# merkur-osdgruve-42-schield.net
KiCad netlist of a schematic drawn in EAGLE
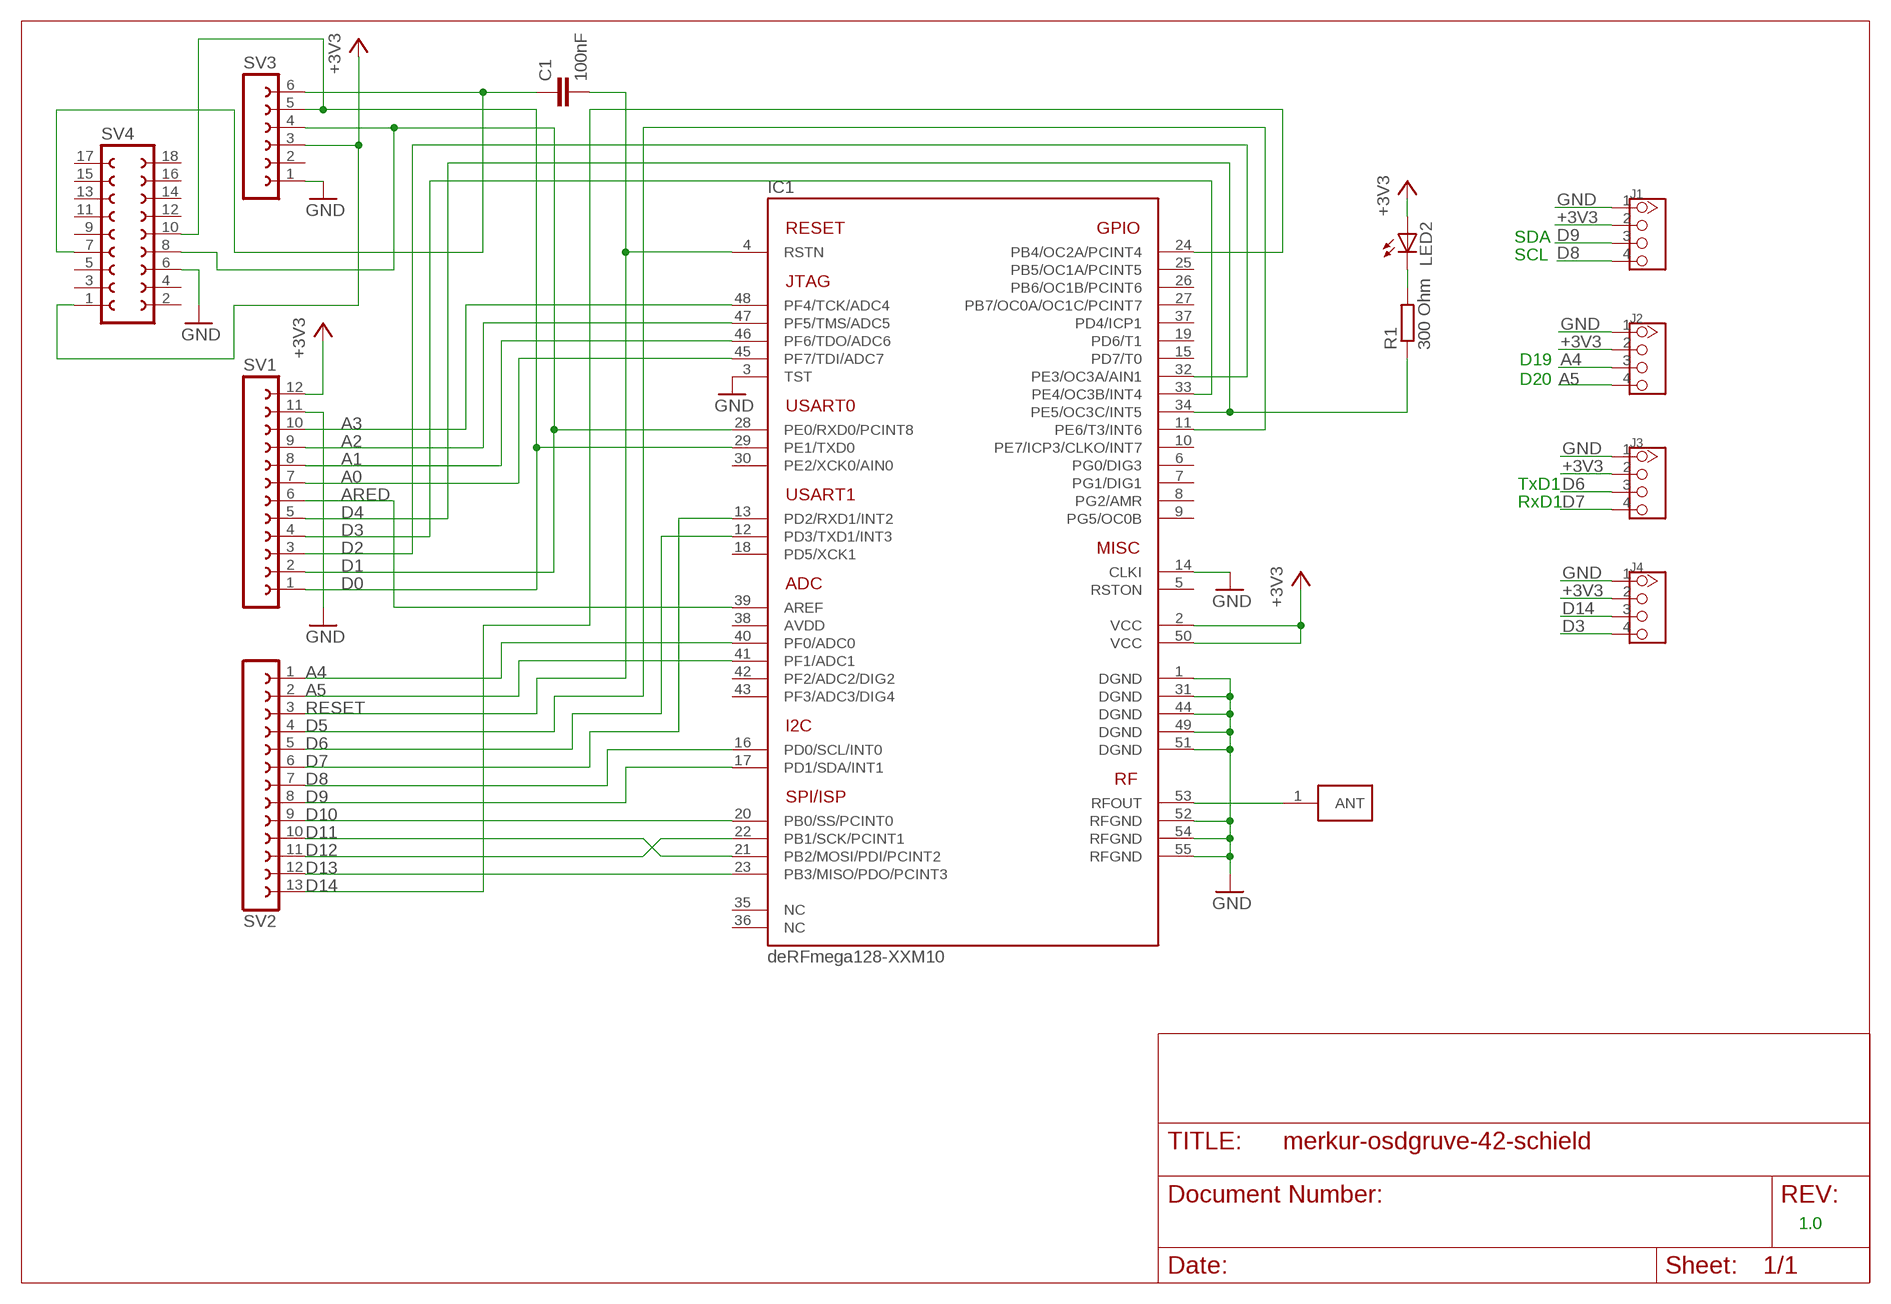
[diagram p0: schematic, sheet 1]

(export (version "E")
  (design (tool "Eeschema 10.0.6"))
  (components
    (comp (ref "C1")
      (value "100nF")
      (footprint "eagle-import:C0603")
      (libsource (lib "eagle-import") (part "C-EUC0603"))
    )
    (comp (ref "IC1")
      (value "DERFMEGA128-XXM10")
      (footprint "eagle-import:A-M10")
      (libsource (lib "eagle-import") (part "DERFMEGA128-XXM10"))
    )
    (comp (ref "J1")
      (value "CONNECTOR_TWIG-4P-2.0-2.0")
      (footprint "eagle-import:CONNECTOR_4P-2.0")
      (libsource (lib "eagle-import") (part "CONNECTOR_TWIG-4P-2.0-2.0"))
    )
    (comp (ref "J2")
      (value "CONNECTOR_TWIG-4P-2.0-2.0")
      (footprint "eagle-import:CONNECTOR_4P-2.0")
      (libsource (lib "eagle-import") (part "CONNECTOR_TWIG-4P-2.0-2.0"))
    )
    (comp (ref "J3")
      (value "CONNECTOR_TWIG-4P-2.0-2.0")
      (footprint "eagle-import:CONNECTOR_4P-2.0")
      (libsource (lib "eagle-import") (part "CONNECTOR_TWIG-4P-2.0-2.0"))
    )
    (comp (ref "J4")
      (value "CONNECTOR_TWIG-4P-2.0-2.0")
      (footprint "eagle-import:CONNECTOR_4P-2.0")
      (libsource (lib "eagle-import") (part "CONNECTOR_TWIG-4P-2.0-2.0"))
    )
    (comp (ref "LED2")
      (value "LEDCHIP-LED0603")
      (footprint "eagle-import:CHIP-LED0603")
      (libsource (lib "eagle-import") (part "LEDCHIP-LED0603"))
    )
    (comp (ref "R1")
      (value "300 Ohm")
      (footprint "eagle-import:R0603")
      (libsource (lib "eagle-import") (part "R-EU_R0603"))
    )
    (comp (ref "SV1")
      (value "FE12-1")
      (footprint "eagle-import:FE12")
      (libsource (lib "eagle-import") (part "FE12-1"))
    )
    (comp (ref "SV2")
      (value "FE13-1")
      (footprint "eagle-import:FE13")
      (libsource (lib "eagle-import") (part "FE13-1"))
    )
    (comp (ref "SV3")
      (value "FE06-1")
      (footprint "eagle-import:FE06")
      (libsource (lib "eagle-import") (part "FE06-1"))
    )
    (comp (ref "SV4")
      (value "FE09-2")
      (footprint "eagle-import:FE09-2")
      (libsource (lib "eagle-import") (part "FE09-2"))
    )
    (comp (ref "U$1")
      (value "PAD")
      (footprint "eagle-import:FE05-1")
      (libsource (lib "eagle-import") (part "PAD"))
    )
  )
  (nets
    (net (code "1") (name "+3V3") (class "Default")
      (node (ref "IC1") (pin "2") (pinfunction "VCC_2") (pintype "power_in"))
      (node (ref "IC1") (pin "50") (pinfunction "VCC_50") (pintype "power_in"))
      (node (ref "J1") (pin "2") (pinfunction "2_2") (pintype "bidirectional"))
      (node (ref "J2") (pin "2") (pinfunction "2_2") (pintype "bidirectional"))
      (node (ref "J3") (pin "2") (pinfunction "2_2") (pintype "bidirectional"))
      (node (ref "J4") (pin "2") (pinfunction "2_2") (pintype "bidirectional"))
      (node (ref "LED2") (pin "A") (pinfunction "A_A") (pintype "passive"))
      (node (ref "SV1") (pin "12") (pinfunction "12_12") (pintype "passive"))
      (node (ref "SV3") (pin "3") (pinfunction "3_3") (pintype "passive"))
      (node (ref "SV4") (pin "1") (pinfunction "1_1") (pintype "passive"))
    )
    (net (code "2") (name "/A0") (class "Default")
      (node (ref "IC1") (pin "45") (pinfunction "PF7/TDI/ADC7_45") (pintype "bidirectional"))
      (node (ref "SV1") (pin "7") (pinfunction "7_7") (pintype "passive"))
    )
    (net (code "3") (name "/A1") (class "Default")
      (node (ref "IC1") (pin "46") (pinfunction "PF6/TDO/ADC6_46") (pintype "bidirectional"))
      (node (ref "SV1") (pin "8") (pinfunction "8_8") (pintype "passive"))
    )
    (net (code "4") (name "/A2") (class "Default")
      (node (ref "IC1") (pin "47") (pinfunction "PF5/TMS/ADC5_47") (pintype "bidirectional"))
      (node (ref "SV1") (pin "9") (pinfunction "9_9") (pintype "passive"))
    )
    (net (code "5") (name "/A3") (class "Default")
      (node (ref "IC1") (pin "48") (pinfunction "PF4/TCK/ADC4_48") (pintype "bidirectional"))
      (node (ref "SV1") (pin "10") (pinfunction "10_10") (pintype "passive"))
    )
    (net (code "6") (name "/A4") (class "Default")
      (node (ref "IC1") (pin "40") (pinfunction "PF0/ADC0_40") (pintype "bidirectional"))
      (node (ref "J2") (pin "3") (pinfunction "3_3") (pintype "bidirectional"))
      (node (ref "SV2") (pin "1") (pinfunction "1_1") (pintype "passive"))
    )
    (net (code "7") (name "/A5") (class "Default")
      (node (ref "IC1") (pin "41") (pinfunction "PF1/ADC1_41") (pintype "bidirectional"))
      (node (ref "J2") (pin "4") (pinfunction "4_4") (pintype "bidirectional"))
      (node (ref "SV2") (pin "2") (pinfunction "2_2") (pintype "passive"))
    )
    (net (code "8") (name "/ARED") (class "Default")
      (node (ref "IC1") (pin "39") (pinfunction "AREF_39") (pintype "bidirectional"))
      (node (ref "SV1") (pin "6") (pinfunction "6_6") (pintype "passive"))
    )
    (net (code "9") (name "/AVDD") (class "Default")
      (node (ref "IC1") (pin "38") (pinfunction "AVDD_38") (pintype "power_in"))
    )
    (net (code "10") (name "/D0") (class "Default")
      (node (ref "IC1") (pin "29") (pinfunction "PE1/TXD0_29") (pintype "bidirectional"))
      (node (ref "SV1") (pin "1") (pinfunction "1_1") (pintype "passive"))
      (node (ref "SV3") (pin "5") (pinfunction "5_5") (pintype "passive"))
      (node (ref "SV4") (pin "10") (pinfunction "10_10") (pintype "passive"))
    )
    (net (code "11") (name "/D1") (class "Default")
      (node (ref "IC1") (pin "28") (pinfunction "PE0/RXD0/PCINT8_28") (pintype "bidirectional"))
      (node (ref "SV1") (pin "2") (pinfunction "2_2") (pintype "passive"))
      (node (ref "SV3") (pin "4") (pinfunction "4_4") (pintype "passive"))
      (node (ref "SV4") (pin "8") (pinfunction "8_8") (pintype "passive"))
    )
    (net (code "12") (name "/D2") (class "Default")
      (node (ref "IC1") (pin "32") (pinfunction "PE3/OC3A/AIN1_32") (pintype "bidirectional"))
      (node (ref "SV1") (pin "3") (pinfunction "3_3") (pintype "passive"))
    )
    (net (code "13") (name "/D3") (class "Default")
      (node (ref "IC1") (pin "33") (pinfunction "PE4/OC3B/INT4_33") (pintype "bidirectional"))
      (node (ref "J4") (pin "4") (pinfunction "4_4") (pintype "bidirectional"))
      (node (ref "SV1") (pin "4") (pinfunction "4_4") (pintype "passive"))
    )
    (net (code "14") (name "/D4") (class "Default")
      (node (ref "IC1") (pin "34") (pinfunction "PE5/OC3C/INT5_34") (pintype "bidirectional"))
      (node (ref "R1") (pin "1") (pinfunction "1_1") (pintype "passive"))
      (node (ref "SV1") (pin "5") (pinfunction "5_5") (pintype "passive"))
    )
    (net (code "15") (name "/D5") (class "Default")
      (node (ref "IC1") (pin "11") (pinfunction "PE6/T3/INT6_11") (pintype "bidirectional"))
      (node (ref "SV2") (pin "4") (pinfunction "4_4") (pintype "passive"))
    )
    (net (code "16") (name "/D6") (class "Default")
      (node (ref "IC1") (pin "12") (pinfunction "PD3/TXD1/INT3_12") (pintype "bidirectional"))
      (node (ref "J3") (pin "3") (pinfunction "3_3") (pintype "bidirectional"))
      (node (ref "SV2") (pin "5") (pinfunction "5_5") (pintype "passive"))
    )
    (net (code "17") (name "/D7") (class "Default")
      (node (ref "IC1") (pin "13") (pinfunction "PD2/RXD1/INT2_13") (pintype "bidirectional"))
      (node (ref "J3") (pin "4") (pinfunction "4_4") (pintype "bidirectional"))
      (node (ref "SV2") (pin "6") (pinfunction "6_6") (pintype "passive"))
    )
    (net (code "18") (name "/D8") (class "Default")
      (node (ref "IC1") (pin "16") (pinfunction "PD0/SCL/INT0_16") (pintype "bidirectional"))
      (node (ref "J1") (pin "4") (pinfunction "4_4") (pintype "bidirectional"))
      (node (ref "SV2") (pin "7") (pinfunction "7_7") (pintype "passive"))
    )
    (net (code "19") (name "/D9") (class "Default")
      (node (ref "IC1") (pin "17") (pinfunction "PD1/SDA/INT1_17") (pintype "bidirectional"))
      (node (ref "J1") (pin "3") (pinfunction "3_3") (pintype "bidirectional"))
      (node (ref "SV2") (pin "8") (pinfunction "8_8") (pintype "passive"))
    )
    (net (code "20") (name "/D10") (class "Default")
      (node (ref "IC1") (pin "20") (pinfunction "PB0/SS/PCINT0_20") (pintype "bidirectional"))
      (node (ref "SV2") (pin "9") (pinfunction "9_9") (pintype "passive"))
    )
    (net (code "21") (name "/D11") (class "Default")
      (node (ref "IC1") (pin "21") (pinfunction "PB2/MOSI/PDI/PCINT2_21") (pintype "bidirectional"))
      (node (ref "SV2") (pin "10") (pinfunction "10_10") (pintype "passive"))
    )
    (net (code "22") (name "/D12") (class "Default")
      (node (ref "IC1") (pin "22") (pinfunction "PB1/SCK/PCINT1_22") (pintype "bidirectional"))
      (node (ref "SV2") (pin "11") (pinfunction "11_11") (pintype "passive"))
    )
    (net (code "23") (name "/D13") (class "Default")
      (node (ref "IC1") (pin "23") (pinfunction "PB3/MISO/PDO/PCINT3_23") (pintype "bidirectional"))
      (node (ref "SV2") (pin "12") (pinfunction "12_12") (pintype "passive"))
    )
    (net (code "24") (name "/D14") (class "Default")
      (node (ref "IC1") (pin "24") (pinfunction "PB4/OC2A/PCINT4_24") (pintype "bidirectional"))
      (node (ref "J4") (pin "3") (pinfunction "3_3") (pintype "bidirectional"))
      (node (ref "SV2") (pin "13") (pinfunction "13_13") (pintype "passive"))
    )
    (net (code "25") (name "/RESET") (class "Default")
      (node (ref "C1") (pin "2") (pinfunction "2_2") (pintype "passive"))
      (node (ref "IC1") (pin "4") (pinfunction "RSTN_4") (pintype "input"))
      (node (ref "SV2") (pin "3") (pinfunction "3_3") (pintype "passive"))
    )
    (net (code "26") (name "GND") (class "Default")
      (node (ref "IC1") (pin "1") (pinfunction "DGND_1") (pintype "power_in"))
      (node (ref "IC1") (pin "14") (pinfunction "CLKI_14") (pintype "input"))
      (node (ref "IC1") (pin "3") (pinfunction "TST_3") (pintype "bidirectional"))
      (node (ref "IC1") (pin "31") (pinfunction "DGND_31") (pintype "power_in"))
      (node (ref "IC1") (pin "44") (pinfunction "DGND_44") (pintype "power_in"))
      (node (ref "IC1") (pin "49") (pinfunction "DGND_49") (pintype "power_in"))
      (node (ref "IC1") (pin "51") (pinfunction "DGND_51") (pintype "power_in"))
      (node (ref "IC1") (pin "52") (pinfunction "RFGND_52") (pintype "power_in"))
      (node (ref "IC1") (pin "54") (pinfunction "RFGND_54") (pintype "power_in"))
      (node (ref "IC1") (pin "55") (pinfunction "RFGND_55") (pintype "power_in"))
      (node (ref "J1") (pin "1") (pinfunction "1_1") (pintype "bidirectional"))
      (node (ref "J2") (pin "1") (pinfunction "1_1") (pintype "bidirectional"))
      (node (ref "J3") (pin "1") (pinfunction "1_1") (pintype "bidirectional"))
      (node (ref "J4") (pin "1") (pinfunction "1_1") (pintype "bidirectional"))
      (node (ref "SV1") (pin "11") (pinfunction "11_11") (pintype "passive"))
      (node (ref "SV3") (pin "1") (pinfunction "1_1") (pintype "passive"))
      (node (ref "SV4") (pin "6") (pinfunction "6_6") (pintype "passive"))
    )
    (net (code "27") (name "Net-(C1-Pad1)") (class "Default")
      (node (ref "C1") (pin "1") (pinfunction "1_1") (pintype "passive"))
      (node (ref "SV3") (pin "6") (pinfunction "6_6") (pintype "passive"))
      (node (ref "SV4") (pin "7") (pinfunction "7_7") (pintype "passive"))
    )
    (net (code "28") (name "Net-(IC1-RFOUT)") (class "Default")
      (node (ref "IC1") (pin "53") (pinfunction "RFOUT_53") (pintype "power_in"))
      (node (ref "U$1") (pin "1") (pinfunction "ANT_1") (pintype "output"))
    )
    (net (code "29") (name "Net-(LED2-PadC)") (class "Default")
      (node (ref "LED2") (pin "C") (pinfunction "C_C") (pintype "passive"))
      (node (ref "R1") (pin "2") (pinfunction "2_2") (pintype "passive"))
    )
    (net (code "30") (name "unconnected-(IC1-NC-Pad35)") (class "Default")
      (node (ref "IC1") (pin "35") (pinfunction "NC_35") (pintype "no_connect"))
    )
    (net (code "31") (name "unconnected-(IC1-NC-Pad36)") (class "Default")
      (node (ref "IC1") (pin "36") (pinfunction "NC_36") (pintype "no_connect"))
    )
    (net (code "32") (name "unconnected-(IC1-PB5{slash}OC1A{slash}PCINT5-Pad25)") (class "Default")
      (node (ref "IC1") (pin "25") (pinfunction "PB5/OC1A/PCINT5_25") (pintype "bidirectional"))
    )
    (net (code "33") (name "unconnected-(IC1-PB6{slash}OC1B{slash}PCINT6-Pad26)") (class "Default")
      (node (ref "IC1") (pin "26") (pinfunction "PB6/OC1B/PCINT6_26") (pintype "bidirectional"))
    )
    (net (code "34") (name "unconnected-(IC1-PB7{slash}OC0A{slash}OC1C{slash}PCINT7-Pad27)") (class "Default")
      (node (ref "IC1") (pin "27") (pinfunction "PB7/OC0A/OC1C/PCINT7_27") (pintype "bidirectional"))
    )
    (net (code "35") (name "unconnected-(IC1-PD4{slash}ICP1-Pad37)") (class "Default")
      (node (ref "IC1") (pin "37") (pinfunction "PD4/ICP1_37") (pintype "bidirectional"))
    )
    (net (code "36") (name "unconnected-(IC1-PD5{slash}XCK1-Pad18)") (class "Default")
      (node (ref "IC1") (pin "18") (pinfunction "PD5/XCK1_18") (pintype "bidirectional"))
    )
    (net (code "37") (name "unconnected-(IC1-PD6{slash}T1-Pad19)") (class "Default")
      (node (ref "IC1") (pin "19") (pinfunction "PD6/T1_19") (pintype "bidirectional"))
    )
    (net (code "38") (name "unconnected-(IC1-PD7{slash}T0-Pad15)") (class "Default")
      (node (ref "IC1") (pin "15") (pinfunction "PD7/T0_15") (pintype "bidirectional"))
    )
    (net (code "39") (name "unconnected-(IC1-PE2{slash}XCK0{slash}AIN0-Pad30)") (class "Default")
      (node (ref "IC1") (pin "30") (pinfunction "PE2/XCK0/AIN0_30") (pintype "bidirectional"))
    )
    (net (code "40") (name "unconnected-(IC1-PE7{slash}ICP3{slash}CLKO{slash}INT7-Pad10)") (class "Default")
      (node (ref "IC1") (pin "10") (pinfunction "PE7/ICP3/CLKO/INT7_10") (pintype "bidirectional"))
    )
    (net (code "41") (name "unconnected-(IC1-PF2{slash}ADC2{slash}DIG2-Pad42)") (class "Default")
      (node (ref "IC1") (pin "42") (pinfunction "PF2/ADC2/DIG2_42") (pintype "bidirectional"))
    )
    (net (code "42") (name "unconnected-(IC1-PF3{slash}ADC3{slash}DIG4-Pad43)") (class "Default")
      (node (ref "IC1") (pin "43") (pinfunction "PF3/ADC3/DIG4_43") (pintype "bidirectional"))
    )
    (net (code "43") (name "unconnected-(IC1-PG0{slash}DIG3-Pad6)") (class "Default")
      (node (ref "IC1") (pin "6") (pinfunction "PG0/DIG3_6") (pintype "bidirectional"))
    )
    (net (code "44") (name "unconnected-(IC1-PG1{slash}DIG1-Pad7)") (class "Default")
      (node (ref "IC1") (pin "7") (pinfunction "PG1/DIG1_7") (pintype "bidirectional"))
    )
    (net (code "45") (name "unconnected-(IC1-PG2{slash}AMR-Pad8)") (class "Default")
      (node (ref "IC1") (pin "8") (pinfunction "PG2/AMR_8") (pintype "bidirectional"))
    )
    (net (code "46") (name "unconnected-(IC1-PG5{slash}OC0B-Pad9)") (class "Default")
      (node (ref "IC1") (pin "9") (pinfunction "PG5/OC0B_9") (pintype "bidirectional"))
    )
    (net (code "47") (name "unconnected-(IC1-RSTON-Pad5)") (class "Default")
      (node (ref "IC1") (pin "5") (pinfunction "RSTON_5") (pintype "output"))
    )
    (net (code "48") (name "unconnected-(SV3-Pad2)") (class "Default")
      (node (ref "SV3") (pin "2") (pinfunction "2_2") (pintype "passive"))
    )
    (net (code "49") (name "unconnected-(SV4-Pad2)") (class "Default")
      (node (ref "SV4") (pin "2") (pinfunction "2_2") (pintype "passive"))
    )
    (net (code "50") (name "unconnected-(SV4-Pad3)") (class "Default")
      (node (ref "SV4") (pin "3") (pinfunction "3_3") (pintype "passive"))
    )
    (net (code "51") (name "unconnected-(SV4-Pad4)") (class "Default")
      (node (ref "SV4") (pin "4") (pinfunction "4_4") (pintype "passive"))
    )
    (net (code "52") (name "unconnected-(SV4-Pad5)") (class "Default")
      (node (ref "SV4") (pin "5") (pinfunction "5_5") (pintype "passive"))
    )
    (net (code "53") (name "unconnected-(SV4-Pad9)") (class "Default")
      (node (ref "SV4") (pin "9") (pinfunction "9_9") (pintype "passive"))
    )
    (net (code "54") (name "unconnected-(SV4-Pad11)") (class "Default")
      (node (ref "SV4") (pin "11") (pinfunction "11_11") (pintype "passive"))
    )
    (net (code "55") (name "unconnected-(SV4-Pad12)") (class "Default")
      (node (ref "SV4") (pin "12") (pinfunction "12_12") (pintype "passive"))
    )
    (net (code "56") (name "unconnected-(SV4-Pad13)") (class "Default")
      (node (ref "SV4") (pin "13") (pinfunction "13_13") (pintype "passive"))
    )
    (net (code "57") (name "unconnected-(SV4-Pad14)") (class "Default")
      (node (ref "SV4") (pin "14") (pinfunction "14_14") (pintype "passive"))
    )
    (net (code "58") (name "unconnected-(SV4-Pad15)") (class "Default")
      (node (ref "SV4") (pin "15") (pinfunction "15_15") (pintype "passive"))
    )
    (net (code "59") (name "unconnected-(SV4-Pad16)") (class "Default")
      (node (ref "SV4") (pin "16") (pinfunction "16_16") (pintype "passive"))
    )
    (net (code "60") (name "unconnected-(SV4-Pad17)") (class "Default")
      (node (ref "SV4") (pin "17") (pinfunction "17_17") (pintype "passive"))
    )
    (net (code "61") (name "unconnected-(SV4-Pad18)") (class "Default")
      (node (ref "SV4") (pin "18") (pinfunction "18_18") (pintype "passive"))
    )
  )
)
